# 202004A830.net
KiCad netlist of a schematic drawn in Altium Designer
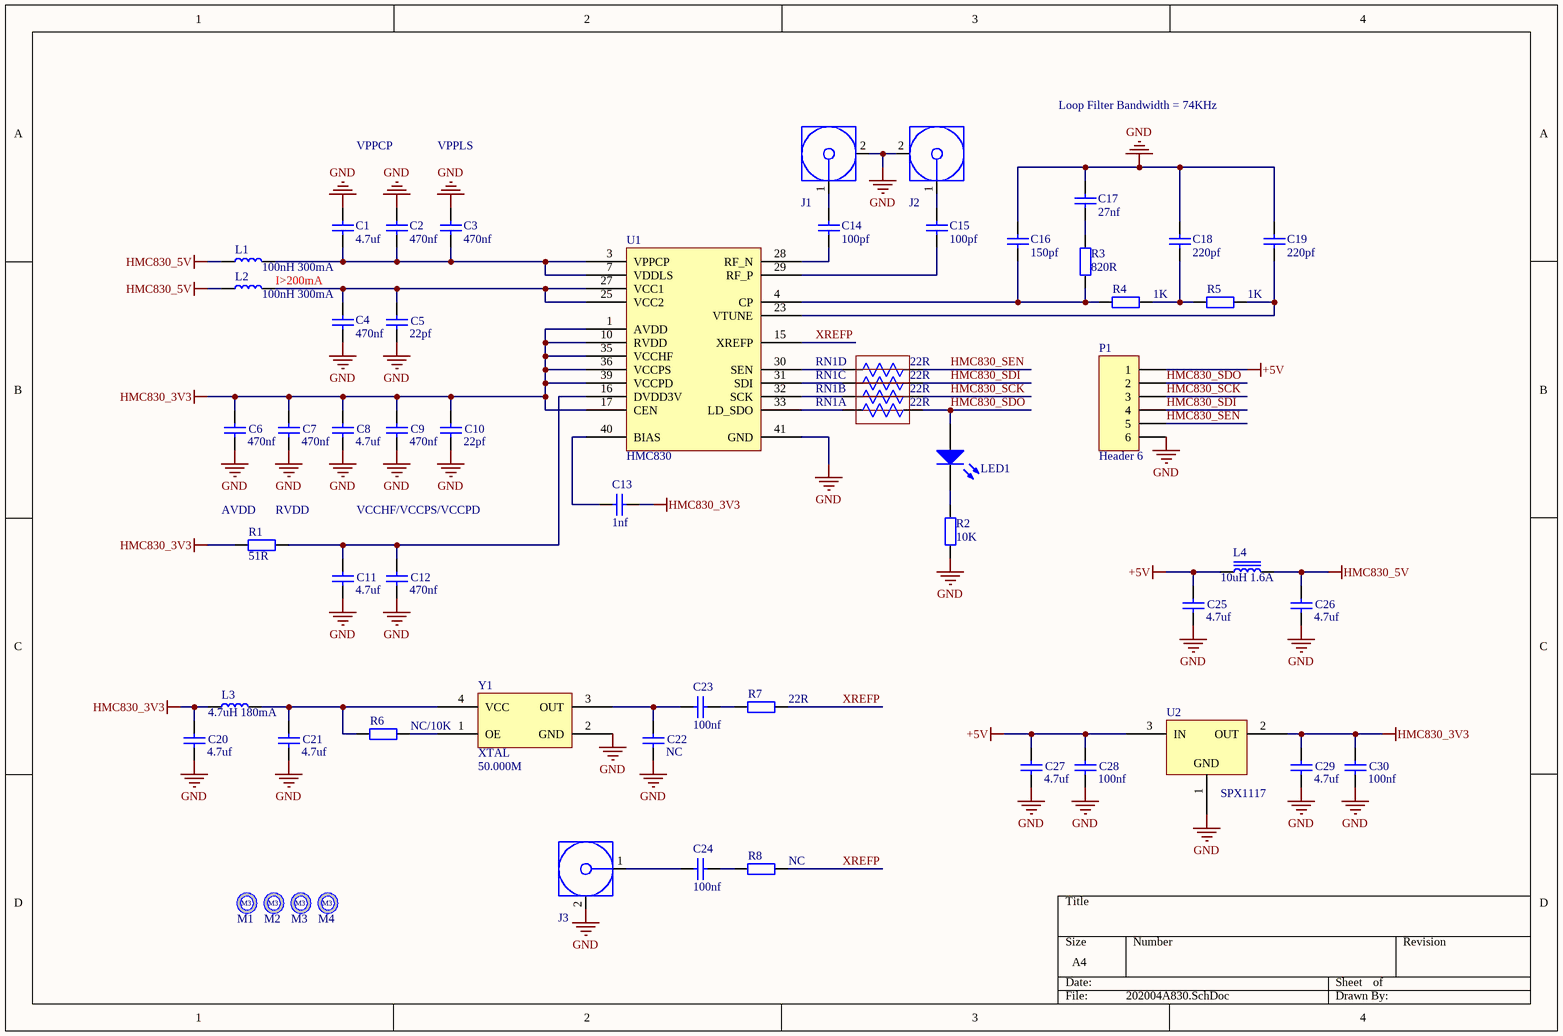
[diagram p0: 202004A830.SchDoc]

(export (version "E")
  (design (tool "Eeschema 10.0.6"))
  (components
    (comp (ref "C1")
      (value "4.7uf")
      (footprint "C0805")
      (fields (field (name "Comment") "Cap"))
      (libsource (lib "carrot_lib") (part "Cap"))
    )
    (comp (ref "C2")
      (value "470nf")
      (footprint "C0805")
      (fields (field (name "Comment") "Cap"))
      (libsource (lib "carrot_lib") (part "Cap"))
    )
    (comp (ref "C3")
      (value "470nf")
      (footprint "C0805")
      (fields (field (name "Comment") "Cap"))
      (libsource (lib "carrot_lib") (part "Cap"))
    )
    (comp (ref "C4")
      (value "470nf")
      (footprint "C0805")
      (fields (field (name "Comment") "Cap"))
      (libsource (lib "carrot_lib") (part "Cap"))
    )
    (comp (ref "C5")
      (value "22pf")
      (footprint "C0805")
      (fields (field (name "Comment") "Cap"))
      (libsource (lib "carrot_lib") (part "Cap"))
    )
    (comp (ref "C6")
      (value "470nf")
      (footprint "C0805")
      (fields (field (name "Comment") "Cap"))
      (libsource (lib "carrot_lib") (part "Cap"))
    )
    (comp (ref "C7")
      (value "470nf")
      (footprint "C0805")
      (fields (field (name "Comment") "Cap"))
      (libsource (lib "carrot_lib") (part "Cap"))
    )
    (comp (ref "C8")
      (value "4.7uf")
      (footprint "C0805")
      (fields (field (name "Comment") "Cap"))
      (libsource (lib "carrot_lib") (part "Cap"))
    )
    (comp (ref "C9")
      (value "470nf")
      (footprint "C0805")
      (fields (field (name "Comment") "Cap"))
      (libsource (lib "carrot_lib") (part "Cap"))
    )
    (comp (ref "C10")
      (value "22pf")
      (footprint "C0805")
      (fields (field (name "Comment") "Cap"))
      (libsource (lib "carrot_lib") (part "Cap"))
    )
    (comp (ref "C11")
      (value "4.7uf")
      (footprint "C0805")
      (fields (field (name "Comment") "Cap"))
      (libsource (lib "carrot_lib") (part "Cap"))
    )
    (comp (ref "C12")
      (value "470nf")
      (footprint "C0805")
      (fields (field (name "Comment") "Cap"))
      (libsource (lib "carrot_lib") (part "Cap"))
    )
    (comp (ref "C13")
      (value "1nf")
      (footprint "C0805")
      (fields (field (name "Comment") "Cap"))
      (libsource (lib "carrot_lib") (part "Cap"))
    )
    (comp (ref "C14")
      (value "100pf")
      (footprint "C0805")
      (fields (field (name "Comment") "Cap"))
      (libsource (lib "carrot_lib") (part "Cap"))
    )
    (comp (ref "C15")
      (value "100pf")
      (footprint "C0805")
      (fields (field (name "Comment") "Cap"))
      (libsource (lib "carrot_lib") (part "Cap"))
    )
    (comp (ref "C16")
      (value "150pf")
      (footprint "C0805")
      (fields (field (name "Comment") "Cap"))
      (libsource (lib "carrot_lib") (part "Cap"))
    )
    (comp (ref "C17")
      (value "27nf")
      (footprint "C0805")
      (fields (field (name "Comment") "Cap"))
      (libsource (lib "carrot_lib") (part "Cap"))
    )
    (comp (ref "C18")
      (value "220pf")
      (footprint "C0805")
      (fields (field (name "Comment") "Cap"))
      (libsource (lib "carrot_lib") (part "Cap"))
    )
    (comp (ref "C19")
      (value "220pf")
      (footprint "C0805")
      (fields (field (name "Comment") "Cap"))
      (libsource (lib "carrot_lib") (part "Cap"))
    )
    (comp (ref "C20")
      (value "4.7uf")
      (footprint "C0805")
      (fields (field (name "Comment") "Cap"))
      (libsource (lib "carrot_lib") (part "Cap"))
    )
    (comp (ref "C21")
      (value "4.7uf")
      (footprint "C0805")
      (fields (field (name "Comment") "Cap"))
      (libsource (lib "carrot_lib") (part "Cap"))
    )
    (comp (ref "C22")
      (value "NC")
      (footprint "C0805")
      (fields (field (name "Comment") "Cap"))
      (libsource (lib "carrot_lib") (part "Cap"))
    )
    (comp (ref "C23")
      (value "100nf")
      (footprint "C0805")
      (fields (field (name "Comment") "Cap"))
      (libsource (lib "carrot_lib") (part "Cap"))
    )
    (comp (ref "C24")
      (value "100nf")
      (footprint "C0805")
      (fields (field (name "Comment") "Cap"))
      (libsource (lib "carrot_lib") (part "Cap"))
    )
    (comp (ref "C25")
      (value "4.7uf")
      (footprint "C0805")
      (fields (field (name "Comment") "Cap"))
      (libsource (lib "carrot_lib") (part "Cap"))
    )
    (comp (ref "C26")
      (value "4.7uf")
      (footprint "C0805")
      (fields (field (name "Comment") "Cap"))
      (libsource (lib "carrot_lib") (part "Cap"))
    )
    (comp (ref "C27")
      (value "4.7uf")
      (footprint "C0805")
      (fields (field (name "Comment") "Cap"))
      (libsource (lib "carrot_lib") (part "Cap"))
    )
    (comp (ref "C28")
      (value "100nf")
      (footprint "C0805")
      (fields (field (name "Comment") "Cap"))
      (libsource (lib "carrot_lib") (part "Cap"))
    )
    (comp (ref "C29")
      (value "4.7uf")
      (footprint "C0805")
      (fields (field (name "Comment") "Cap"))
      (libsource (lib "carrot_lib") (part "Cap"))
    )
    (comp (ref "C30")
      (value "100nf")
      (footprint "C0805")
      (fields (field (name "Comment") "Cap"))
      (libsource (lib "carrot_lib") (part "Cap"))
    )
    (comp (ref "J1") (value "SMA") (footprint "SMA-3") (libsource (lib "carrot_lib") (part "SMA")))
    (comp (ref "J2") (value "SMA") (footprint "SMA-3") (libsource (lib "carrot_lib") (part "SMA")))
    (comp (ref "J3") (value "SMA") (footprint "SMA-3") (libsource (lib "carrot_lib") (part "SMA")))
    (comp (ref "L1")
      (value "100nH 300mA")
      (footprint "L0805HQ")
      (description "Chip Inductor")
      (fields (field (name "Comment") "Inductor Chip"))
      (libsource (lib "carrot_lib") (part "Inductor Chip"))
    )
    (comp (ref "L2")
      (value "100nH 300mA")
      (footprint "L0805HQ")
      (description "Chip Inductor")
      (fields (field (name "Comment") "Inductor Chip"))
      (libsource (lib "carrot_lib") (part "Inductor Chip"))
    )
    (comp (ref "L3")
      (value "4.7uH 180mA")
      (footprint "L0805HQ")
      (description "Chip Inductor")
      (fields (field (name "Comment") "Inductor Chip"))
      (libsource (lib "carrot_lib") (part "Inductor Chip"))
    )
    (comp (ref "L4")
      (value "10uH 1.6A")
      (footprint "L4020")
      (description "Magnetic-Core Inductor")
      (fields (field (name "Comment") "Inductor Iron"))
      (libsource (lib "carrot_lib") (part "Inductor Iron"))
    )
    (comp (ref "LED1") (value "LED") (footprint "LED1206") (libsource (lib "carrot_lib") (part "LED")))
    (comp (ref "M1") (value "M3") (footprint "M3-3.2X5") (libsource (lib "carrot_lib") (part "M3")))
    (comp (ref "M2") (value "M3") (footprint "M3-3.2X5") (libsource (lib "carrot_lib") (part "M3")))
    (comp (ref "M3") (value "M3") (footprint "M3-3.2X5") (libsource (lib "carrot_lib") (part "M3")))
    (comp (ref "M4") (value "M3") (footprint "M3-3.2X5") (libsource (lib "carrot_lib") (part "M3")))
    (comp (ref "P1")
      (value "Header 6")
      (footprint "HDR1X6")
      (description "Header, 6-Pin")
      (fields (field (name "PUBLISHER") "Altium Limited"))
      (libsource (lib "Miscellaneous Connectors") (part "Header 6"))
    )
    (comp (ref "R1")
      (value "51R")
      (footprint "R0805")
      (description "电阻")
      (fields (field (name "Comment") "Res"))
      (libsource (lib "") (part "Res_2"))
    )
    (comp (ref "R2")
      (value "10K")
      (footprint "R0805")
      (description "电阻")
      (fields (field (name "Comment") "Res"))
      (libsource (lib "carrot_lib") (part "Res"))
    )
    (comp (ref "R3")
      (value "820R")
      (footprint "R0805")
      (description "电阻")
      (fields (field (name "Comment") "Res"))
      (libsource (lib "") (part "Res_3"))
    )
    (comp (ref "R4")
      (value "1K")
      (footprint "R0805")
      (description "电阻")
      (fields (field (name "Comment") "Res"))
      (libsource (lib "") (part "Res_1"))
    )
    (comp (ref "R5")
      (value "1K")
      (footprint "R0805")
      (description "电阻")
      (fields (field (name "Comment") "Res"))
      (libsource (lib "") (part "Res_1"))
    )
    (comp (ref "R6")
      (value "NC/10K")
      (footprint "R0805")
      (description "电阻")
      (fields (field (name "Comment") "Res"))
      (libsource (lib "") (part "Res_1"))
    )
    (comp (ref "R7")
      (value "22R")
      (footprint "R0805")
      (description "电阻")
      (fields (field (name "Comment") "Res"))
      (libsource (lib "") (part "Res_1"))
    )
    (comp (ref "R8")
      (value "NC")
      (footprint "R0805")
      (description "电阻")
      (fields (field (name "Comment") "Res"))
      (libsource (lib "") (part "Res_1"))
    )
    (comp (ref "RN1")
      (value "22R")
      (footprint "RA0603")
      (description "贴片排阻")
      (fields (field (name "Comment") "Res Array"))
      (libsource (lib "carrot_lib") (part "Res Array 2"))
    )
    (comp (ref "U1")
      (value "HMC830")
      (footprint "HMC830")
      (description "Fractional-N PLL with Integrated VCO, 25 - 3000 MHz")
      (libsource (lib "carrot_lib") (part "HMC830"))
    )
    (comp (ref "U2")
      (value "SPX1117")
      (footprint "SPX1117-SOT223")
      (description "800mA Low Dropout Voltage Regulator")
      (libsource (lib "carrot_lib") (part "SPX1117"))
    )
    (comp (ref "Y1")
      (value "XTAL")
      (footprint "XTAL-3225")
      (description "有源晶振")
      (fields (field (name "ALTIUM_VALUE") "50.000M"))
      (libsource (lib "carrot_lib") (part "XTAL2"))
    )
  )
  (nets
    (net (code "1") (name "+5V") (class "Default")
      (node (ref "C25") (pin "2") (pinfunction "2_2") (pintype "passive"))
      (node (ref "C27") (pin "2") (pinfunction "2_2") (pintype "passive"))
      (node (ref "C28") (pin "2") (pinfunction "2_2") (pintype "passive"))
      (node (ref "L4") (pin "1") (pinfunction "1_1") (pintype "passive"))
      (node (ref "P1") (pin "1") (pinfunction "1_1") (pintype "passive"))
      (node (ref "U2") (pin "3") (pinfunction "IN_3") (pintype "passive"))
    )
    (net (code "2") (name "/HMC830_SCK") (class "Default")
      (node (ref "P1") (pin "3") (pinfunction "3_3") (pintype "passive"))
      (node (ref "RN1") (pin "7") (pinfunction "7_7") (pintype "passive"))
    )
    (net (code "3") (name "/HMC830_SDI") (class "Default")
      (node (ref "P1") (pin "4") (pinfunction "4_4") (pintype "passive"))
      (node (ref "RN1") (pin "6") (pinfunction "6_6") (pintype "passive"))
    )
    (net (code "4") (name "/HMC830_SDO") (class "Default")
      (node (ref "LED1") (pin "1") (pinfunction "A_1") (pintype "passive"))
      (node (ref "P1") (pin "2") (pinfunction "2_2") (pintype "passive"))
      (node (ref "RN1") (pin "8") (pinfunction "8_8") (pintype "passive"))
    )
    (net (code "5") (name "/HMC830_SEN") (class "Default")
      (node (ref "P1") (pin "5") (pinfunction "5_5") (pintype "passive"))
      (node (ref "RN1") (pin "5") (pinfunction "5_5") (pintype "passive"))
    )
    (net (code "6") (name "/XREFP") (class "Default")
      (node (ref "R7") (pin "1") (pinfunction "1_1") (pintype "passive"))
      (node (ref "R8") (pin "1") (pinfunction "1_1") (pintype "passive"))
      (node (ref "U1") (pin "15") (pinfunction "XREFP_15") (pintype "passive"))
    )
    (net (code "7") (name "GND") (class "Default")
      (node (ref "C1") (pin "1") (pinfunction "1_1") (pintype "passive"))
      (node (ref "C10") (pin "1") (pinfunction "1_1") (pintype "passive"))
      (node (ref "C11") (pin "1") (pinfunction "1_1") (pintype "passive"))
      (node (ref "C12") (pin "1") (pinfunction "1_1") (pintype "passive"))
      (node (ref "C16") (pin "2") (pinfunction "2_2") (pintype "passive"))
      (node (ref "C17") (pin "2") (pinfunction "2_2") (pintype "passive"))
      (node (ref "C18") (pin "2") (pinfunction "2_2") (pintype "passive"))
      (node (ref "C19") (pin "2") (pinfunction "2_2") (pintype "passive"))
      (node (ref "C2") (pin "1") (pinfunction "1_1") (pintype "passive"))
      (node (ref "C20") (pin "1") (pinfunction "1_1") (pintype "passive"))
      (node (ref "C21") (pin "1") (pinfunction "1_1") (pintype "passive"))
      (node (ref "C22") (pin "1") (pinfunction "1_1") (pintype "passive"))
      (node (ref "C25") (pin "1") (pinfunction "1_1") (pintype "passive"))
      (node (ref "C26") (pin "1") (pinfunction "1_1") (pintype "passive"))
      (node (ref "C27") (pin "1") (pinfunction "1_1") (pintype "passive"))
      (node (ref "C28") (pin "1") (pinfunction "1_1") (pintype "passive"))
      (node (ref "C29") (pin "1") (pinfunction "1_1") (pintype "passive"))
      (node (ref "C3") (pin "1") (pinfunction "1_1") (pintype "passive"))
      (node (ref "C30") (pin "1") (pinfunction "1_1") (pintype "passive"))
      (node (ref "C4") (pin "1") (pinfunction "1_1") (pintype "passive"))
      (node (ref "C5") (pin "1") (pinfunction "1_1") (pintype "passive"))
      (node (ref "C6") (pin "1") (pinfunction "1_1") (pintype "passive"))
      (node (ref "C7") (pin "1") (pinfunction "1_1") (pintype "passive"))
      (node (ref "C8") (pin "1") (pinfunction "1_1") (pintype "passive"))
      (node (ref "C9") (pin "1") (pinfunction "1_1") (pintype "passive"))
      (node (ref "J1") (pin "2") (pinfunction "GND_2") (pintype "power_in"))
      (node (ref "J2") (pin "2") (pinfunction "GND_2") (pintype "power_in"))
      (node (ref "J3") (pin "2") (pinfunction "GND_2") (pintype "power_in"))
      (node (ref "P1") (pin "6") (pinfunction "6_6") (pintype "passive"))
      (node (ref "R2") (pin "1") (pinfunction "1_1") (pintype "passive"))
      (node (ref "U1") (pin "41") (pinfunction "GND_41") (pintype "passive"))
      (node (ref "U2") (pin "1") (pinfunction "GND_1") (pintype "passive"))
      (node (ref "Y1") (pin "2") (pinfunction "GND_2") (pintype "passive"))
    )
    (net (code "8") (name "HMC830_3V3") (class "Default")
      (node (ref "C10") (pin "2") (pinfunction "2_2") (pintype "passive"))
      (node (ref "C13") (pin "1") (pinfunction "1_1") (pintype "passive"))
      (node (ref "C20") (pin "2") (pinfunction "2_2") (pintype "passive"))
      (node (ref "C29") (pin "2") (pinfunction "2_2") (pintype "passive"))
      (node (ref "C30") (pin "2") (pinfunction "2_2") (pintype "passive"))
      (node (ref "C6") (pin "2") (pinfunction "2_2") (pintype "passive"))
      (node (ref "C7") (pin "2") (pinfunction "2_2") (pintype "passive"))
      (node (ref "C8") (pin "2") (pinfunction "2_2") (pintype "passive"))
      (node (ref "C9") (pin "2") (pinfunction "2_2") (pintype "passive"))
      (node (ref "L3") (pin "1") (pinfunction "1_1") (pintype "passive"))
      (node (ref "R1") (pin "1") (pinfunction "1_1") (pintype "passive"))
      (node (ref "U1") (pin "1") (pinfunction "AVDD_1") (pintype "passive"))
      (node (ref "U1") (pin "10") (pinfunction "RVDD_10") (pintype "passive"))
      (node (ref "U1") (pin "17") (pinfunction "CEN_17") (pintype "passive"))
      (node (ref "U1") (pin "35") (pinfunction "VCCHF_35") (pintype "passive"))
      (node (ref "U1") (pin "36") (pinfunction "VCCPS_36") (pintype "passive"))
      (node (ref "U1") (pin "39") (pinfunction "VCCPD_39") (pintype "passive"))
      (node (ref "U2") (pin "2") (pinfunction "OUT_2") (pintype "passive"))
    )
    (net (code "9") (name "HMC830_5V") (class "Default")
      (node (ref "C26") (pin "2") (pinfunction "2_2") (pintype "passive"))
      (node (ref "L1") (pin "1") (pinfunction "1_1") (pintype "passive"))
      (node (ref "L2") (pin "1") (pinfunction "1_1") (pintype "passive"))
      (node (ref "L4") (pin "2") (pinfunction "2_2") (pintype "passive"))
    )
    (net (code "10") (name "Net-(C17-Pad1)") (class "Default")
      (node (ref "C17") (pin "1") (pinfunction "1_1") (pintype "passive"))
      (node (ref "R3") (pin "1") (pinfunction "1_1") (pintype "passive"))
    )
    (net (code "11") (name "Net-(C18-Pad1)") (class "Default")
      (node (ref "C18") (pin "1") (pinfunction "1_1") (pintype "passive"))
      (node (ref "R4") (pin "1") (pinfunction "1_1") (pintype "passive"))
      (node (ref "R5") (pin "2") (pinfunction "2_2") (pintype "passive"))
    )
    (net (code "12") (name "Net-(C23-Pad1)") (class "Default")
      (node (ref "C23") (pin "1") (pinfunction "1_1") (pintype "passive"))
      (node (ref "R7") (pin "2") (pinfunction "2_2") (pintype "passive"))
    )
    (net (code "13") (name "Net-(C24-Pad1)") (class "Default")
      (node (ref "C24") (pin "1") (pinfunction "1_1") (pintype "passive"))
      (node (ref "R8") (pin "2") (pinfunction "2_2") (pintype "passive"))
    )
    (net (code "14") (name "Net-(J1-Signal)") (class "Default")
      (node (ref "C14") (pin "1") (pinfunction "1_1") (pintype "passive"))
      (node (ref "J1") (pin "1") (pinfunction "Signal_1") (pintype "power_in"))
    )
    (net (code "15") (name "Net-(J2-Signal)") (class "Default")
      (node (ref "C15") (pin "1") (pinfunction "1_1") (pintype "passive"))
      (node (ref "J2") (pin "1") (pinfunction "Signal_1") (pintype "power_in"))
    )
    (net (code "16") (name "Net-(J3-Signal)") (class "Default")
      (node (ref "C24") (pin "2") (pinfunction "2_2") (pintype "passive"))
      (node (ref "J3") (pin "1") (pinfunction "Signal_1") (pintype "power_in"))
    )
    (net (code "17") (name "Net-(LED1-K)") (class "Default")
      (node (ref "LED1") (pin "2") (pinfunction "K_2") (pintype "passive"))
      (node (ref "R2") (pin "2") (pinfunction "2_2") (pintype "passive"))
    )
    (net (code "18") (name "Net-(U1-BIAS)") (class "Default")
      (node (ref "C13") (pin "2") (pinfunction "2_2") (pintype "passive"))
      (node (ref "U1") (pin "40") (pinfunction "BIAS_40") (pintype "passive"))
    )
    (net (code "19") (name "Net-(U1-CP)") (class "Default")
      (node (ref "C16") (pin "1") (pinfunction "1_1") (pintype "passive"))
      (node (ref "R3") (pin "2") (pinfunction "2_2") (pintype "passive"))
      (node (ref "R4") (pin "2") (pinfunction "2_2") (pintype "passive"))
      (node (ref "U1") (pin "4") (pinfunction "CP_4") (pintype "passive"))
    )
    (net (code "20") (name "Net-(U1-DVDD3V)") (class "Default")
      (node (ref "C11") (pin "2") (pinfunction "2_2") (pintype "passive"))
      (node (ref "C12") (pin "2") (pinfunction "2_2") (pintype "passive"))
      (node (ref "R1") (pin "2") (pinfunction "2_2") (pintype "passive"))
      (node (ref "U1") (pin "16") (pinfunction "DVDD3V_16") (pintype "passive"))
    )
    (net (code "21") (name "Net-(U1-LD_SDO)") (class "Default")
      (node (ref "RN1") (pin "1") (pinfunction "1_1") (pintype "passive"))
      (node (ref "U1") (pin "33") (pinfunction "LD_SDO_33") (pintype "passive"))
    )
    (net (code "22") (name "Net-(U1-RF_N)") (class "Default")
      (node (ref "C14") (pin "2") (pinfunction "2_2") (pintype "passive"))
      (node (ref "U1") (pin "28") (pinfunction "RF_N_28") (pintype "passive"))
    )
    (net (code "23") (name "Net-(U1-RF_P)") (class "Default")
      (node (ref "C15") (pin "2") (pinfunction "2_2") (pintype "passive"))
      (node (ref "U1") (pin "29") (pinfunction "RF_P_29") (pintype "passive"))
    )
    (net (code "24") (name "Net-(U1-SCK)") (class "Default")
      (node (ref "RN1") (pin "2") (pinfunction "2_2") (pintype "passive"))
      (node (ref "U1") (pin "32") (pinfunction "SCK_32") (pintype "passive"))
    )
    (net (code "25") (name "Net-(U1-SDI)") (class "Default")
      (node (ref "RN1") (pin "3") (pinfunction "3_3") (pintype "passive"))
      (node (ref "U1") (pin "31") (pinfunction "SDI_31") (pintype "passive"))
    )
    (net (code "26") (name "Net-(U1-SEN)") (class "Default")
      (node (ref "RN1") (pin "4") (pinfunction "4_4") (pintype "passive"))
      (node (ref "U1") (pin "30") (pinfunction "SEN_30") (pintype "passive"))
    )
    (net (code "27") (name "Net-(U1-VCC1)") (class "Default")
      (node (ref "C4") (pin "2") (pinfunction "2_2") (pintype "passive"))
      (node (ref "C5") (pin "2") (pinfunction "2_2") (pintype "passive"))
      (node (ref "L2") (pin "2") (pinfunction "2_2") (pintype "passive"))
      (node (ref "U1") (pin "25") (pinfunction "VCC2_25") (pintype "passive"))
      (node (ref "U1") (pin "27") (pinfunction "VCC1_27") (pintype "passive"))
    )
    (net (code "28") (name "Net-(U1-VDDLS)") (class "Default")
      (node (ref "C1") (pin "2") (pinfunction "2_2") (pintype "passive"))
      (node (ref "C2") (pin "2") (pinfunction "2_2") (pintype "passive"))
      (node (ref "C3") (pin "2") (pinfunction "2_2") (pintype "passive"))
      (node (ref "L1") (pin "2") (pinfunction "2_2") (pintype "passive"))
      (node (ref "U1") (pin "3") (pinfunction "VPPCP_3") (pintype "passive"))
      (node (ref "U1") (pin "7") (pinfunction "VDDLS_7") (pintype "passive"))
    )
    (net (code "29") (name "Net-(U1-VTUNE)") (class "Default")
      (node (ref "C19") (pin "1") (pinfunction "1_1") (pintype "passive"))
      (node (ref "R5") (pin "1") (pinfunction "1_1") (pintype "passive"))
      (node (ref "U1") (pin "23") (pinfunction "VTUNE_23") (pintype "passive"))
    )
    (net (code "30") (name "Net-(Y1-OE)") (class "Default")
      (node (ref "R6") (pin "1") (pinfunction "1_1") (pintype "passive"))
      (node (ref "Y1") (pin "1") (pinfunction "OE_1") (pintype "passive"))
    )
    (net (code "31") (name "Net-(Y1-OUT)") (class "Default")
      (node (ref "C22") (pin "2") (pinfunction "2_2") (pintype "passive"))
      (node (ref "C23") (pin "2") (pinfunction "2_2") (pintype "passive"))
      (node (ref "Y1") (pin "3") (pinfunction "OUT_3") (pintype "passive"))
    )
    (net (code "32") (name "Net-(Y1-VCC)") (class "Default")
      (node (ref "C21") (pin "2") (pinfunction "2_2") (pintype "passive"))
      (node (ref "L3") (pin "2") (pinfunction "2_2") (pintype "passive"))
      (node (ref "R6") (pin "2") (pinfunction "2_2") (pintype "passive"))
      (node (ref "Y1") (pin "4") (pinfunction "VCC_4") (pintype "passive"))
    )
  )
)
